# MCP2515_PINOUT.net
KiCad netlist of a schematic drawn in Altium Designer
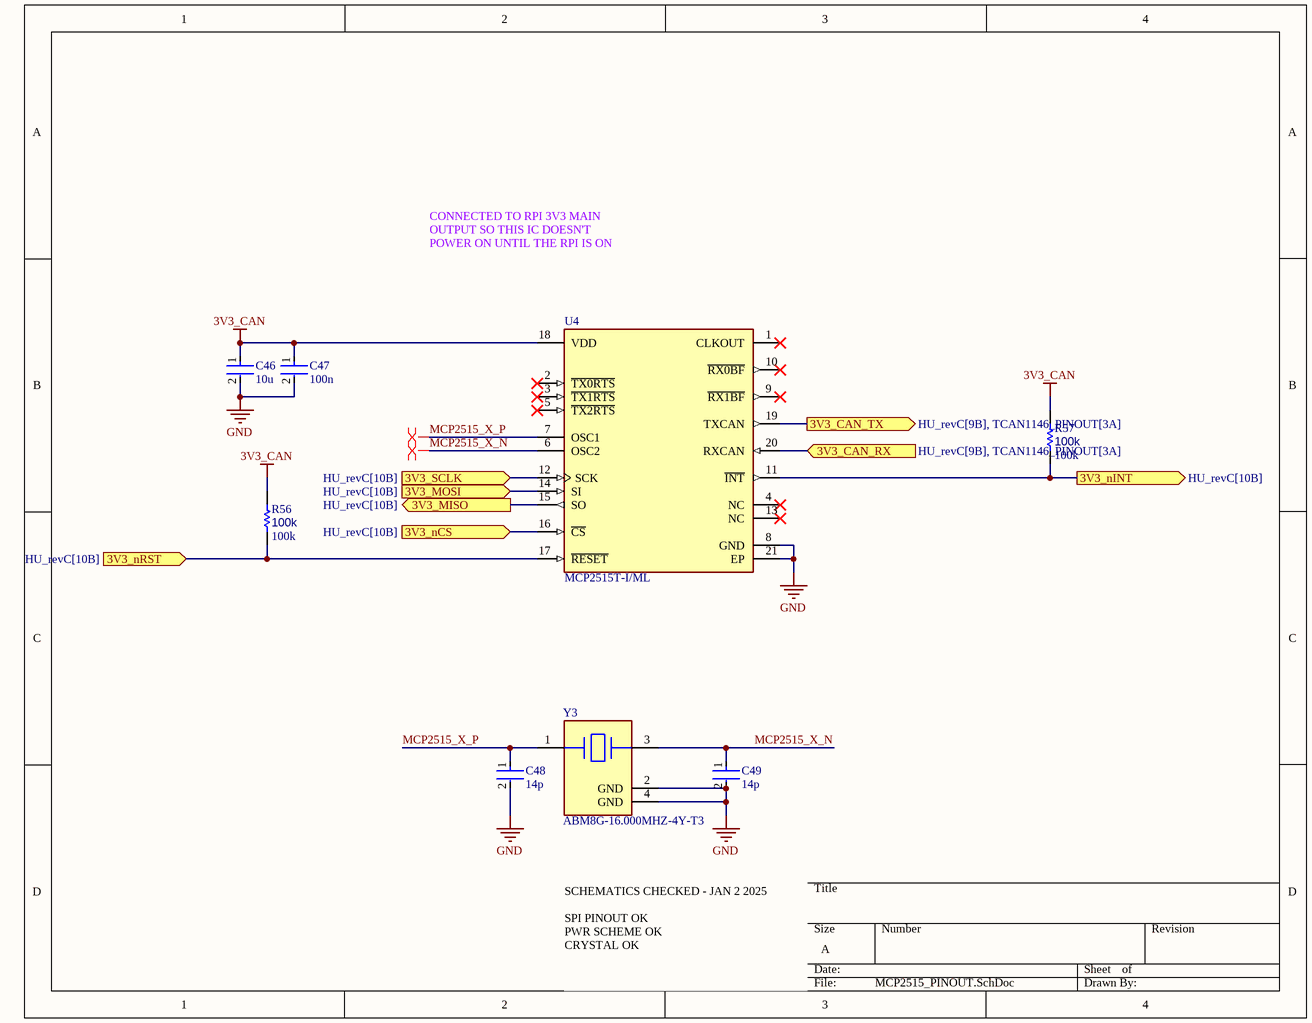
[diagram p0: MCP2515_PINOUT.SchDoc]

(export (version "E")
  (design (tool "Eeschema 10.0.6"))
  (components
    (comp (ref "C46")
      (value "10u")
      (footprint "FP-0402-L_1_0_0_05-W_0_5-IPC_A")
      (description "LARGE PADS, 0402 CAP, CHANGE COMMENT TO MATCH REAL P/N")
      (libsource (lib "Space Concordia") (part "b4654b650e69147ec39a6b967a45e02"))
    )
    (comp (ref "C47")
      (value "100n")
      (footprint "FP-0402-L_1_0_0_05-W_0_5-IPC_A")
      (description "LARGE PADS, 0402 CAP, CHANGE COMMENT TO MATCH REAL P/N")
      (libsource (lib "Space Concordia") (part "b4654b650e69147ec39a6b967a45e02"))
    )
    (comp (ref "C48")
      (value "14p")
      (footprint "FP-0402-L_1_0_0_05-W_0_5-IPC_A")
      (description "LARGE PADS, 0402 CAP, CHANGE COMMENT TO MATCH REAL P/N")
      (libsource (lib "Space Concordia") (part "b4654b650e69147ec39a6b967a45e02"))
    )
    (comp (ref "C49")
      (value "14p")
      (footprint "FP-0402-L_1_0_0_05-W_0_5-IPC_A")
      (description "LARGE PADS, 0402 CAP, CHANGE COMMENT TO MATCH REAL P/N")
      (libsource (lib "Space Concordia") (part "b4654b650e69147ec39a6b967a45e02"))
    )
    (comp (ref "R56")
      (value "100k")
      (footprint "R0603B")
      (description "Resistor")
      (fields (field (name "ALTIUM_VALUE") "100k"))
      (libsource (lib "Space Concordia") (part "Resistor"))
    )
    (comp (ref "R57")
      (value "100k")
      (footprint "R0603B")
      (description "Resistor")
      (fields (field (name "ALTIUM_VALUE") "100k"))
      (libsource (lib "Space Concordia") (part "Resistor"))
    )
    (comp (ref "U4")
      (value "MCP2515T-I/ML")
      (footprint "FP-C04-126-MFG")
      (description "IC CAN CTLR W/SPI 2.0B 20-QFN")
      (libsource (lib "Altium Content Vault") (part "593a678ea5bfa0b9d28ded8e5851c80"))
    )
    (comp (ref "Y3")
      (value "ABM8G-16.000MHZ-4Y-T3")
      (footprint "FP-ABM8G-MFG")
      (description "Crystal 16MHz ±30ppm (Tol) ±30ppm (Stability) 10pF FUND 80Ω 4-Pin SMD T/R")
      (libsource (lib "Altium Content Vault") (part "48e526d86b7f2615d98721063c72f49"))
    )
  )
  (nets
    (net (code "1") (name "/3V3_CAN_RX") (class "Default")
      (node (ref "U4") (pin "20") (pinfunction "RXCAN_20") (pintype "input"))
    )
    (net (code "2") (name "/3V3_CAN_TX") (class "Default")
      (node (ref "U4") (pin "19") (pinfunction "TXCAN_19") (pintype "output"))
    )
    (net (code "3") (name "/3V3_MISO") (class "Default")
      (node (ref "U4") (pin "15") (pinfunction "SO_15") (pintype "output"))
    )
    (net (code "4") (name "/3V3_MOSI") (class "Default")
      (node (ref "U4") (pin "14") (pinfunction "SI_14") (pintype "input"))
    )
    (net (code "5") (name "/3V3_SCLK") (class "Default")
      (node (ref "U4") (pin "12") (pinfunction "SCK_12") (pintype "input"))
    )
    (net (code "6") (name "/3V3_nCS") (class "Default")
      (node (ref "U4") (pin "16") (pinfunction "~{CS}_16") (pintype "input"))
    )
    (net (code "7") (name "/3V3_nINT") (class "Default")
      (node (ref "R57") (pin "2") (pinfunction "2_2") (pintype "passive"))
      (node (ref "U4") (pin "11") (pinfunction "~{INT}_11") (pintype "output"))
    )
    (net (code "8") (name "/3V3_nRST") (class "Default")
      (node (ref "R56") (pin "2") (pinfunction "2_2") (pintype "passive"))
      (node (ref "U4") (pin "17") (pinfunction "~{RESET}_17") (pintype "input"))
    )
    (net (code "9") (name "/MCP2515_X_N") (class "Default")
      (node (ref "C49") (pin "1") (pinfunction "1_1") (pintype "passive"))
      (node (ref "U4") (pin "6") (pinfunction "OSC2_6") (pintype "passive"))
      (node (ref "Y3") (pin "3") (pinfunction "3_3") (pintype "passive"))
    )
    (net (code "10") (name "/MCP2515_X_P") (class "Default")
      (node (ref "C48") (pin "1") (pinfunction "1_1") (pintype "passive"))
      (node (ref "U4") (pin "7") (pinfunction "OSC1_7") (pintype "passive"))
      (node (ref "Y3") (pin "1") (pinfunction "1_1") (pintype "passive"))
    )
    (net (code "11") (name "3V3_CAN") (class "Default")
      (node (ref "C46") (pin "1") (pinfunction "1_1") (pintype "passive"))
      (node (ref "C47") (pin "1") (pinfunction "1_1") (pintype "passive"))
      (node (ref "R56") (pin "1") (pinfunction "1_1") (pintype "passive"))
      (node (ref "R57") (pin "1") (pinfunction "1_1") (pintype "passive"))
      (node (ref "U4") (pin "18") (pinfunction "VDD_18") (pintype "power_in"))
    )
    (net (code "12") (name "GND") (class "Default")
      (node (ref "C46") (pin "2") (pinfunction "2_2") (pintype "passive"))
      (node (ref "C47") (pin "2") (pinfunction "2_2") (pintype "passive"))
      (node (ref "C48") (pin "2") (pinfunction "2_2") (pintype "passive"))
      (node (ref "C49") (pin "2") (pinfunction "2_2") (pintype "passive"))
      (node (ref "U4") (pin "21") (pinfunction "EP_21") (pintype "passive"))
      (node (ref "U4") (pin "8") (pinfunction "GND_8") (pintype "power_in"))
      (node (ref "Y3") (pin "2") (pinfunction "GND_2") (pintype "power_in"))
      (node (ref "Y3") (pin "4") (pinfunction "GND_4") (pintype "power_in"))
    )
    (net (code "13") (name "unconnected-(U4-CLKOUT-Pad1)") (class "Default")
      (node (ref "U4") (pin "1") (pinfunction "CLKOUT_1") (pintype "passive+no_connect"))
    )
    (net (code "14") (name "unconnected-(U4-NC-Pad4)") (class "Default")
      (node (ref "U4") (pin "4") (pinfunction "NC_4") (pintype "passive+no_connect"))
    )
    (net (code "15") (name "unconnected-(U4-NC-Pad13)") (class "Default")
      (node (ref "U4") (pin "13") (pinfunction "NC_13") (pintype "passive+no_connect"))
    )
    (net (code "16") (name "unconnected-(U4-~{RX0BF}-Pad10)") (class "Default")
      (node (ref "U4") (pin "10") (pinfunction "~{RX0BF}_10") (pintype "output+no_connect"))
    )
    (net (code "17") (name "unconnected-(U4-~{RX1BF}-Pad9)") (class "Default")
      (node (ref "U4") (pin "9") (pinfunction "~{RX1BF}_9") (pintype "output+no_connect"))
    )
    (net (code "18") (name "unconnected-(U4-~{TX0RTS}-Pad2)") (class "Default")
      (node (ref "U4") (pin "2") (pinfunction "~{TX0RTS}_2") (pintype "input+no_connect"))
    )
    (net (code "19") (name "unconnected-(U4-~{TX1RTS}-Pad3)") (class "Default")
      (node (ref "U4") (pin "3") (pinfunction "~{TX1RTS}_3") (pintype "input+no_connect"))
    )
    (net (code "20") (name "unconnected-(U4-~{TX2RTS}-Pad5)") (class "Default")
      (node (ref "U4") (pin "5") (pinfunction "~{TX2RTS}_5") (pintype "input+no_connect"))
    )
  )
)
